# supply.net
KiCad netlist of a schematic drawn in Altium Designer
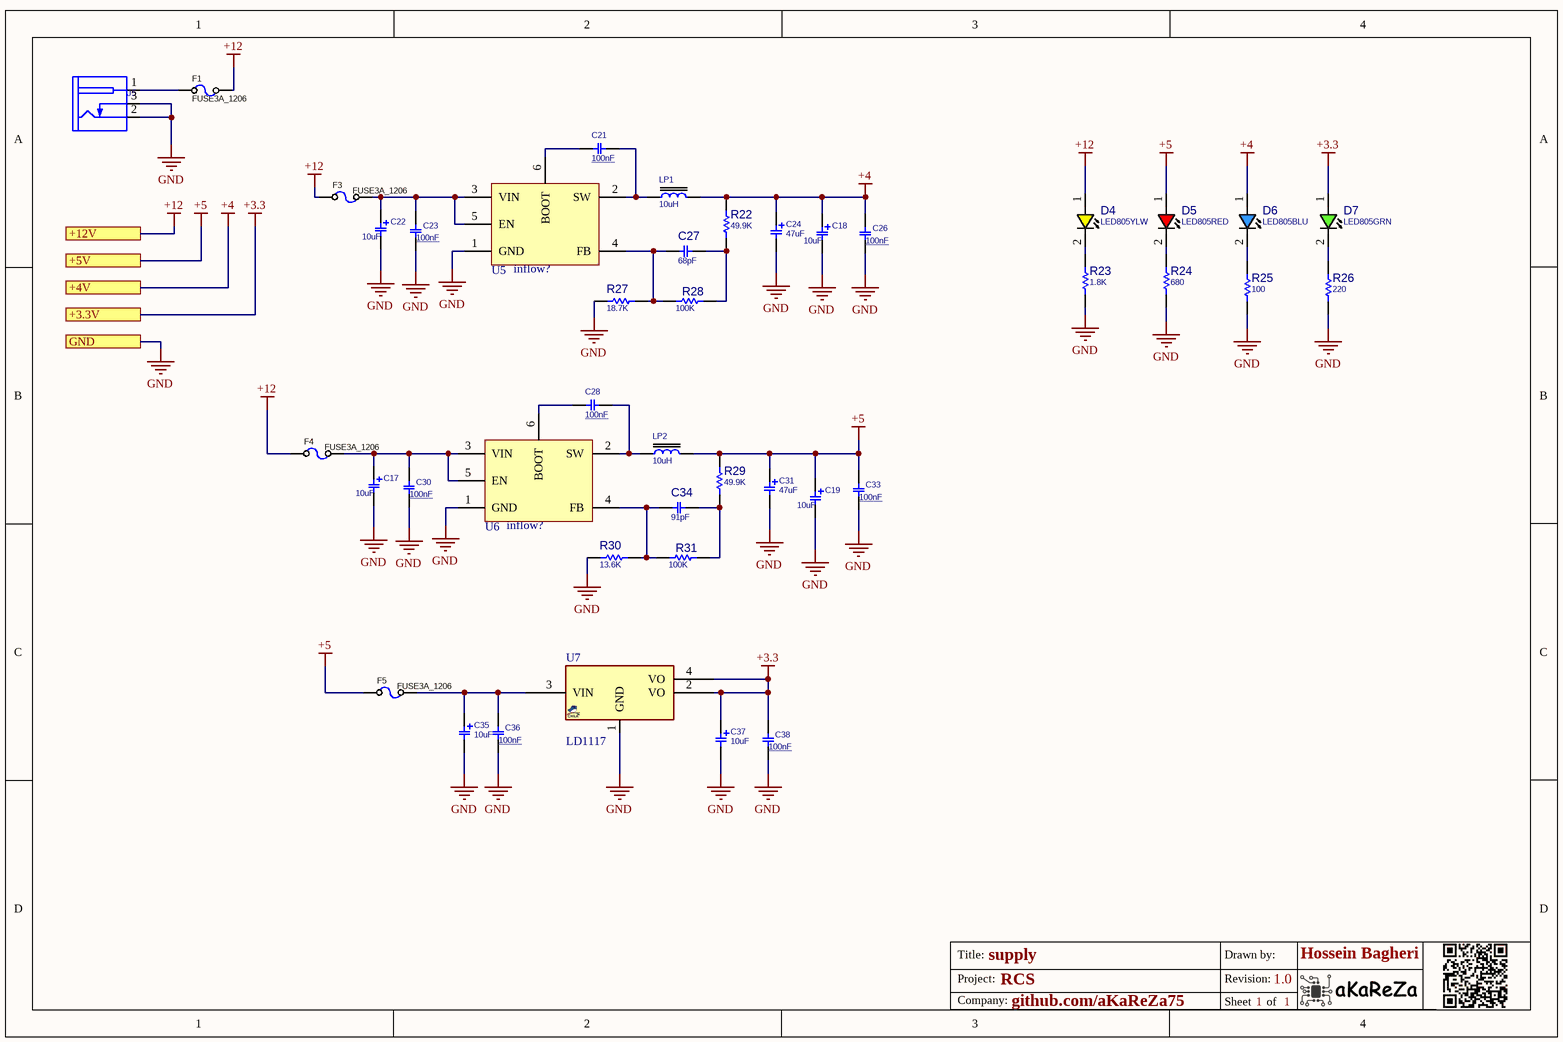
[diagram p0: supply.SchDoc]

(export (version "E")
  (design (tool "Eeschema 10.0.6"))
  (components
    (comp (ref "C17")
      (value "10uF")
      (footprint "C_TN_3528")
      (description "CAP, SMD, TAN")
      (fields (field (name "MANF") "AVX") (field (name "MANF_P#") "TCJT106M016R0200"))
      (libsource (lib "Chila_PCB") (part "CAP_SMD_TAN_10uF_16V"))
    )
    (comp (ref "C18")
      (value "10uF")
      (footprint "C_TN_3528")
      (description "CAP, SMD, TAN")
      (fields (field (name "MANF") "AVX") (field (name "MANF_P#") "TCJT106M016R0200"))
      (libsource (lib "Chila_PCB") (part "CAP_SMD_TAN_10uF_16V"))
    )
    (comp (ref "C19")
      (value "10uF")
      (footprint "C_TN_3528")
      (description "CAP, SMD, TAN")
      (fields (field (name "MANF") "AVX") (field (name "MANF_P#") "TCJT106M016R0200"))
      (libsource (lib "Chila_PCB") (part "CAP_SMD_TAN_10uF_16V"))
    )
    (comp (ref "C21")
      (value "100nF")
      (footprint "C1206")
      (description "CAP, MLCC, -F, -V, MATERIAL, -%, 0201")
      (fields (field (name "MANF_P#") "MANF_PART#"))
      (libsource (lib "Chila_PCB") (part "CAP_SMD_MLCC_1206"))
    )
    (comp (ref "C22")
      (value "10uF")
      (footprint "C_TN_3528")
      (description "CAP, SMD, TAN")
      (fields (field (name "MANF") "AVX") (field (name "MANF_P#") "TCJT106M016R0200"))
      (libsource (lib "Chila_PCB") (part "CAP_SMD_TAN_10uF_16V"))
    )
    (comp (ref "C23")
      (value "100nF")
      (footprint "C1206")
      (description "CAP, MLCC, -F, -V, MATERIAL, -%, 0201")
      (fields (field (name "MANF_P#") "MANF_PART#"))
      (libsource (lib "Chila_PCB") (part "CAP_SMD_MLCC_1206"))
    )
    (comp (ref "C24")
      (value "47uF")
      (footprint "C_TN_2012")
      (description "CAP, SMD, TAN,")
      (libsource (lib "Chila_PCB") (part "CAP_SMD_TAN"))
    )
    (comp (ref "C26")
      (value "100nF")
      (footprint "C1206")
      (description "CAP, MLCC, -F, -V, MATERIAL, -%, 0201")
      (fields (field (name "MANF_P#") "MANF_PART#"))
      (libsource (lib "Chila_PCB") (part "CAP_SMD_MLCC_1206"))
    )
    (comp (ref "C27")
      (value "68pF")
      (footprint "C0805")
      (description "CAP, MLCC")
      (fields (field (name "MANF_P#") "UMK212ABJ225KG-T") (field (name "MANF") "Taiyo Yuden"))
      (libsource (lib "Chila_PCB") (part "CAP_SMD_MLCC_2.2u50V_0805"))
    )
    (comp (ref "C28")
      (value "100nF")
      (footprint "C1206")
      (description "CAP, MLCC, -F, -V, MATERIAL, -%, 0201")
      (fields (field (name "MANF_P#") "MANF_PART#"))
      (libsource (lib "Chila_PCB") (part "CAP_SMD_MLCC_1206"))
    )
    (comp (ref "C30")
      (value "100nF")
      (footprint "C1206")
      (description "CAP, MLCC, -F, -V, MATERIAL, -%, 0201")
      (fields (field (name "MANF_P#") "MANF_PART#"))
      (libsource (lib "Chila_PCB") (part "CAP_SMD_MLCC_1206"))
    )
    (comp (ref "C31")
      (value "47uF")
      (footprint "C_TN_2012")
      (description "CAP, SMD, TAN,")
      (libsource (lib "Chila_PCB") (part "CAP_SMD_TAN"))
    )
    (comp (ref "C33")
      (value "100nF")
      (footprint "C1206")
      (description "CAP, MLCC, -F, -V, MATERIAL, -%, 0201")
      (fields (field (name "MANF_P#") "MANF_PART#"))
      (libsource (lib "Chila_PCB") (part "CAP_SMD_MLCC_1206"))
    )
    (comp (ref "C34")
      (value "91pF")
      (footprint "C0805")
      (description "CAP, MLCC")
      (fields (field (name "MANF_P#") "UMK212ABJ225KG-T") (field (name "MANF") "Taiyo Yuden"))
      (libsource (lib "Chila_PCB") (part "CAP_SMD_MLCC_2.2u50V_0805"))
    )
    (comp (ref "C35")
      (value "10uF")
      (footprint "C_TN_2012")
      (description "CAP, SMD, TAN,")
      (libsource (lib "Chila_PCB") (part "CAP_SMD_TAN"))
    )
    (comp (ref "C36")
      (value "100nF")
      (footprint "C1206")
      (description "CAP, MLCC, -F, -V, MATERIAL, -%, 0201")
      (fields (field (name "MANF_P#") "MANF_PART#"))
      (libsource (lib "Chila_PCB") (part "CAP_SMD_MLCC_1206"))
    )
    (comp (ref "C37")
      (value "10uF")
      (footprint "C_TN_2012")
      (description "CAP, SMD, TAN,")
      (libsource (lib "Chila_PCB") (part "CAP_SMD_TAN"))
    )
    (comp (ref "C38")
      (value "100nF")
      (footprint "C1206")
      (description "CAP, MLCC, -F, -V, MATERIAL, -%, 0201")
      (fields (field (name "MANF_P#") "MANF_PART#"))
      (libsource (lib "Chila_PCB") (part "CAP_SMD_MLCC_1206"))
    )
    (comp (ref "D4")
      (value "LED805YLW")
      (footprint "LED0805YLW")
      (description "LED, SMD, 0805, YELLOW")
      (fields (field (name "MANF") "MANF") (field (name "MANF_P#") "MANF_PART#"))
      (libsource (lib "Chila_PCB") (part "LED_SMD_0805_YLW"))
    )
    (comp (ref "D5")
      (value "LED805RED")
      (footprint "LED0805RED")
      (description "LED, SMD, 0805, RED")
      (fields (field (name "MANF") "MANF") (field (name "MANF_P#") "MANF_PART#"))
      (libsource (lib "Chila_PCB") (part "LED_SMD_0805_RED"))
    )
    (comp (ref "D6")
      (value "LED805BLU")
      (footprint "LED0805BLU")
      (description "LED, SMD, 0805, BLUE")
      (fields (field (name "MANF") "MANF") (field (name "MANF_P#") "MANF_PART#"))
      (libsource (lib "Chila_PCB") (part "LED_SMD_0805_BLU"))
    )
    (comp (ref "D7")
      (value "LED805GRN")
      (footprint "LED0805GRN")
      (description "LED, SMD, 0805, GREEN")
      (libsource (lib "Chila_PCB") (part "LED_SMD_0805_GRN"))
    )
    (comp (ref "F1")
      (value "FUSE3A_1206")
      (footprint "F1206")
      (description "Fuse, 3A, 32VDC, 1206, SMD, Slow Blow")
      (fields (field (name "MANF") "Bourns") (field (name "MANF_P#") "SF-1206SP300-2"))
      (libsource (lib "Chila_PCB") (part "FUSE_3A_1206_SLOW"))
    )
    (comp (ref "F3")
      (value "FUSE3A_1206")
      (footprint "F1206")
      (description "Fuse, 3A, 32VDC, 1206, SMD, Slow Blow")
      (fields (field (name "MANF") "Bourns") (field (name "MANF_P#") "SF-1206SP300-2"))
      (libsource (lib "Chila_PCB") (part "FUSE_3A_1206_SLOW"))
    )
    (comp (ref "F4")
      (value "FUSE3A_1206")
      (footprint "F1206")
      (description "Fuse, 3A, 32VDC, 1206, SMD, Slow Blow")
      (fields (field (name "MANF") "Bourns") (field (name "MANF_P#") "SF-1206SP300-2"))
      (libsource (lib "Chila_PCB") (part "FUSE_3A_1206_SLOW"))
    )
    (comp (ref "F5")
      (value "FUSE3A_1206")
      (footprint "F1206")
      (description "Fuse, 3A, 32VDC, 1206, SMD, Slow Blow")
      (fields (field (name "MANF") "Bourns") (field (name "MANF_P#") "SF-1206SP300-2"))
      (libsource (lib "Chila_PCB") (part "FUSE_3A_1206_SLOW"))
    )
    (comp (ref "J5")
      (value "DC_POWER_JACK")
      (footprint "JAC_PWR2")
      (description "CONN, PWR JACK DC, PLUG DIAM 2.0MM RA THD")
      (fields
        (field (name "MANF") "CUI STACK")
        (field (name "MANF_P#") "PJ-202A, PJ-002AH, PJ-102AH, KLDX-0202")
      )
      (libsource (lib "Chila_PCB") (part "CONN_PWR_JACKR2"))
    )
    (comp (ref "LP1")
      (value "10uH")
      (footprint "L_7")
      (description "INDUCTOR, 10uH, 8A (Irms), 10mOhm")
      (fields (field (name "MANF") "Bourns") (field (name "MANF_P#") "SRP7050TA-3R3M"))
      (libsource (lib "Chila_PCB") (part "IND_SMD_3.3uH_8A"))
    )
    (comp (ref "LP2")
      (value "10uH")
      (footprint "L_7")
      (description "INDUCTOR, 10uH, 8A (Irms), 10mOhm")
      (fields (field (name "MANF") "Bourns") (field (name "MANF_P#") "SRP7050TA-3R3M"))
      (libsource (lib "Chila_PCB") (part "IND_SMD_3.3uH_8A"))
    )
    (comp (ref "R22")
      (value "49.9K")
      (footprint "R0805")
      (description "RESISTOR, SMD")
      (libsource (lib "Chila_PCB") (part "RES_SMD_0805"))
    )
    (comp (ref "R23")
      (value "1.8K")
      (footprint "R0805")
      (description "RESISTOR, SMD")
      (libsource (lib "Chila_PCB") (part "RES_SMD_0805"))
    )
    (comp (ref "R24")
      (value "680")
      (footprint "R0805")
      (description "RESISTOR, SMD")
      (libsource (lib "Chila_PCB") (part "RES_SMD_0805"))
    )
    (comp (ref "R25")
      (value "100")
      (footprint "R0805")
      (description "RESISTOR, SMD")
      (libsource (lib "Chila_PCB") (part "RES_SMD_0805"))
    )
    (comp (ref "R26")
      (value "220")
      (footprint "R0805")
      (description "RESISTOR, SMD")
      (libsource (lib "Chila_PCB") (part "RES_SMD_0805"))
    )
    (comp (ref "R27")
      (value "18.7K")
      (footprint "R0805")
      (description "RESISTOR, SMD")
      (libsource (lib "Chila_PCB") (part "RES_SMD_0805"))
    )
    (comp (ref "R28")
      (value "100K")
      (footprint "R0805")
      (description "RESISTOR, SMD")
      (libsource (lib "Chila_PCB") (part "RES_SMD_0805"))
    )
    (comp (ref "R29")
      (value "49.9K")
      (footprint "R0805")
      (description "RESISTOR, SMD")
      (libsource (lib "Chila_PCB") (part "RES_SMD_0805"))
    )
    (comp (ref "R30")
      (value "13.6K")
      (footprint "R0805")
      (description "RESISTOR, SMD")
      (libsource (lib "Chila_PCB") (part "RES_SMD_0805"))
    )
    (comp (ref "R31")
      (value "100K")
      (footprint "R0805")
      (description "RESISTOR, SMD")
      (libsource (lib "Chila_PCB") (part "RES_SMD_0805"))
    )
    (comp (ref "U5")
      (value "Value?")
      (footprint "TPS54302")
      (description "3'A Synchronous Step-Down Converter")
      (fields (field (name "INFLOW") "inflow?") (field (name "VALIDATION") "Valid"))
      (libsource (lib "aKaReZa") (part "IC_Reg_TPS54302"))
    )
    (comp (ref "U6")
      (value "Value?")
      (footprint "TPS54302")
      (description "3'A Synchronous Step-Down Converter")
      (fields (field (name "INFLOW") "inflow?") (field (name "VALIDATION") "Valid"))
      (libsource (lib "aKaReZa") (part "IC_Reg_TPS54302"))
    )
    (comp (ref "U7")
      (value "LD1117")
      (footprint "SOT223_4")
      (description "REG, Linear, LDO1V, 0.8A, SOT-223")
      (fields
        (field (name "MANF_P#") "LD1117, LM1117, AMS1117, TLV1117, REG1117, NCP1117, LT1117, SPX1117")
        (field (name "MANF") "TI, ON, ST")
      )
      (libsource (lib "Chila_PCB") (part "VREG_1117_SOT223"))
    )
  )
  (nets
    (net (code "1") (name "+3.3") (class "Default")
      (node (ref "C37") (pin "1") (pinfunction "1_1") (pintype "passive"))
      (node (ref "C38") (pin "2") (pinfunction "2_2") (pintype "passive"))
      (node (ref "D7") (pin "1") (pinfunction "ANODE_1") (pintype "passive"))
      (node (ref "U7") (pin "2") (pinfunction "VO_2") (pintype "passive"))
      (node (ref "U7") (pin "4") (pinfunction "VO_4") (pintype "passive"))
    )
    (net (code "2") (name "+4") (class "Default")
      (node (ref "C18") (pin "1") (pinfunction "1_1") (pintype "passive"))
      (node (ref "C24") (pin "1") (pinfunction "1_1") (pintype "passive"))
      (node (ref "C26") (pin "2") (pinfunction "2_2") (pintype "passive"))
      (node (ref "D6") (pin "1") (pinfunction "ANODE_1") (pintype "passive"))
      (node (ref "LP1") (pin "2") (pinfunction "2_2") (pintype "passive"))
      (node (ref "R22") (pin "2") (pinfunction "2_2") (pintype "passive"))
    )
    (net (code "3") (name "+5") (class "Default")
      (node (ref "C19") (pin "1") (pinfunction "1_1") (pintype "passive"))
      (node (ref "C31") (pin "1") (pinfunction "1_1") (pintype "passive"))
      (node (ref "C33") (pin "2") (pinfunction "2_2") (pintype "passive"))
      (node (ref "D5") (pin "1") (pinfunction "ANODE_1") (pintype "passive"))
      (node (ref "F5") (pin "1") (pinfunction "1_1") (pintype "passive"))
      (node (ref "LP2") (pin "2") (pinfunction "2_2") (pintype "passive"))
      (node (ref "R29") (pin "2") (pinfunction "2_2") (pintype "passive"))
    )
    (net (code "4") (name "+12") (class "Default")
      (node (ref "D4") (pin "1") (pinfunction "ANODE_1") (pintype "passive"))
      (node (ref "F1") (pin "2") (pinfunction "2_2") (pintype "passive"))
      (node (ref "F3") (pin "1") (pinfunction "1_1") (pintype "passive"))
      (node (ref "F4") (pin "1") (pinfunction "1_1") (pintype "passive"))
    )
    (net (code "5") (name "GND") (class "Default")
      (node (ref "C17") (pin "2") (pinfunction "2_2") (pintype "passive"))
      (node (ref "C18") (pin "2") (pinfunction "2_2") (pintype "passive"))
      (node (ref "C19") (pin "2") (pinfunction "2_2") (pintype "passive"))
      (node (ref "C22") (pin "2") (pinfunction "2_2") (pintype "passive"))
      (node (ref "C23") (pin "1") (pinfunction "1_1") (pintype "passive"))
      (node (ref "C24") (pin "2") (pinfunction "2_2") (pintype "passive"))
      (node (ref "C26") (pin "1") (pinfunction "1_1") (pintype "passive"))
      (node (ref "C30") (pin "1") (pinfunction "1_1") (pintype "passive"))
      (node (ref "C31") (pin "2") (pinfunction "2_2") (pintype "passive"))
      (node (ref "C33") (pin "1") (pinfunction "1_1") (pintype "passive"))
      (node (ref "C35") (pin "2") (pinfunction "2_2") (pintype "passive"))
      (node (ref "C36") (pin "1") (pinfunction "1_1") (pintype "passive"))
      (node (ref "C37") (pin "2") (pinfunction "2_2") (pintype "passive"))
      (node (ref "C38") (pin "1") (pinfunction "1_1") (pintype "passive"))
      (node (ref "J5") (pin "2") (pinfunction "SLEEVE_2") (pintype "power_in"))
      (node (ref "J5") (pin "3") (pinfunction "INSERTION_DET_3") (pintype "power_in"))
      (node (ref "R23") (pin "1") (pinfunction "1_1") (pintype "passive"))
      (node (ref "R24") (pin "1") (pinfunction "1_1") (pintype "passive"))
      (node (ref "R25") (pin "1") (pinfunction "1_1") (pintype "passive"))
      (node (ref "R26") (pin "1") (pinfunction "1_1") (pintype "passive"))
      (node (ref "R27") (pin "1") (pinfunction "1_1") (pintype "passive"))
      (node (ref "R30") (pin "1") (pinfunction "1_1") (pintype "passive"))
      (node (ref "U5") (pin "1") (pinfunction "GND_1") (pintype "power_in"))
      (node (ref "U6") (pin "1") (pinfunction "GND_1") (pintype "power_in"))
      (node (ref "U7") (pin "1") (pinfunction "GND_1") (pintype "passive"))
    )
    (net (code "6") (name "Net-(C27-Pad2)") (class "Default")
      (node (ref "C27") (pin "2") (pinfunction "2_2") (pintype "passive"))
      (node (ref "R22") (pin "1") (pinfunction "1_1") (pintype "passive"))
      (node (ref "R28") (pin "2") (pinfunction "2_2") (pintype "passive"))
    )
    (net (code "7") (name "Net-(C34-Pad2)") (class "Default")
      (node (ref "C34") (pin "2") (pinfunction "2_2") (pintype "passive"))
      (node (ref "R29") (pin "1") (pinfunction "1_1") (pintype "passive"))
      (node (ref "R31") (pin "2") (pinfunction "2_2") (pintype "passive"))
    )
    (net (code "8") (name "Net-(D4-CATHODE)") (class "Default")
      (node (ref "D4") (pin "2") (pinfunction "CATHODE_2") (pintype "passive"))
      (node (ref "R23") (pin "2") (pinfunction "2_2") (pintype "passive"))
    )
    (net (code "9") (name "Net-(D5-CATHODE)") (class "Default")
      (node (ref "D5") (pin "2") (pinfunction "CATHODE_2") (pintype "passive"))
      (node (ref "R24") (pin "2") (pinfunction "2_2") (pintype "passive"))
    )
    (net (code "10") (name "Net-(D6-CATHODE)") (class "Default")
      (node (ref "D6") (pin "2") (pinfunction "CATHODE_2") (pintype "passive"))
      (node (ref "R25") (pin "2") (pinfunction "2_2") (pintype "passive"))
    )
    (net (code "11") (name "Net-(D7-CATHODE)") (class "Default")
      (node (ref "D7") (pin "2") (pinfunction "CATHODE_2") (pintype "passive"))
      (node (ref "R26") (pin "2") (pinfunction "2_2") (pintype "passive"))
    )
    (net (code "12") (name "Net-(J5-TIP)") (class "Default")
      (node (ref "F1") (pin "1") (pinfunction "1_1") (pintype "passive"))
      (node (ref "J5") (pin "1") (pinfunction "TIP_1") (pintype "power_in"))
    )
    (net (code "13") (name "Net-(U5-BOOT)") (class "Default")
      (node (ref "C21") (pin "2") (pinfunction "2_2") (pintype "passive"))
      (node (ref "U5") (pin "6") (pinfunction "BOOT_6") (pintype "power_in"))
    )
    (net (code "14") (name "Net-(U5-EN)") (class "Default")
      (node (ref "C22") (pin "1") (pinfunction "1_1") (pintype "passive"))
      (node (ref "C23") (pin "2") (pinfunction "2_2") (pintype "passive"))
      (node (ref "F3") (pin "2") (pinfunction "2_2") (pintype "passive"))
      (node (ref "U5") (pin "3") (pinfunction "VIN_3") (pintype "power_in"))
      (node (ref "U5") (pin "5") (pinfunction "EN_5") (pintype "power_in"))
    )
    (net (code "15") (name "Net-(U5-FB)") (class "Default")
      (node (ref "C27") (pin "1") (pinfunction "1_1") (pintype "passive"))
      (node (ref "R27") (pin "2") (pinfunction "2_2") (pintype "passive"))
      (node (ref "R28") (pin "1") (pinfunction "1_1") (pintype "passive"))
      (node (ref "U5") (pin "4") (pinfunction "FB_4") (pintype "power_in"))
    )
    (net (code "16") (name "Net-(U5-SW)") (class "Default")
      (node (ref "C21") (pin "1") (pinfunction "1_1") (pintype "passive"))
      (node (ref "LP1") (pin "1") (pinfunction "1_1") (pintype "passive"))
      (node (ref "U5") (pin "2") (pinfunction "SW_2") (pintype "power_in"))
    )
    (net (code "17") (name "Net-(U6-BOOT)") (class "Default")
      (node (ref "C28") (pin "2") (pinfunction "2_2") (pintype "passive"))
      (node (ref "U6") (pin "6") (pinfunction "BOOT_6") (pintype "power_in"))
    )
    (net (code "18") (name "Net-(U6-EN)") (class "Default")
      (node (ref "C17") (pin "1") (pinfunction "1_1") (pintype "passive"))
      (node (ref "C30") (pin "2") (pinfunction "2_2") (pintype "passive"))
      (node (ref "F4") (pin "2") (pinfunction "2_2") (pintype "passive"))
      (node (ref "U6") (pin "3") (pinfunction "VIN_3") (pintype "power_in"))
      (node (ref "U6") (pin "5") (pinfunction "EN_5") (pintype "power_in"))
    )
    (net (code "19") (name "Net-(U6-FB)") (class "Default")
      (node (ref "C34") (pin "1") (pinfunction "1_1") (pintype "passive"))
      (node (ref "R30") (pin "2") (pinfunction "2_2") (pintype "passive"))
      (node (ref "R31") (pin "1") (pinfunction "1_1") (pintype "passive"))
      (node (ref "U6") (pin "4") (pinfunction "FB_4") (pintype "power_in"))
    )
    (net (code "20") (name "Net-(U6-SW)") (class "Default")
      (node (ref "C28") (pin "1") (pinfunction "1_1") (pintype "passive"))
      (node (ref "LP2") (pin "1") (pinfunction "1_1") (pintype "passive"))
      (node (ref "U6") (pin "2") (pinfunction "SW_2") (pintype "power_in"))
    )
    (net (code "21") (name "Net-(U7-VIN)") (class "Default")
      (node (ref "C35") (pin "1") (pinfunction "1_1") (pintype "passive"))
      (node (ref "C36") (pin "2") (pinfunction "2_2") (pintype "passive"))
      (node (ref "F5") (pin "2") (pinfunction "2_2") (pintype "passive"))
      (node (ref "U7") (pin "3") (pinfunction "VIN_3") (pintype "passive"))
    )
  )
)
